# 1_P1.net
KiCad netlist of a schematic drawn in Altium Designer
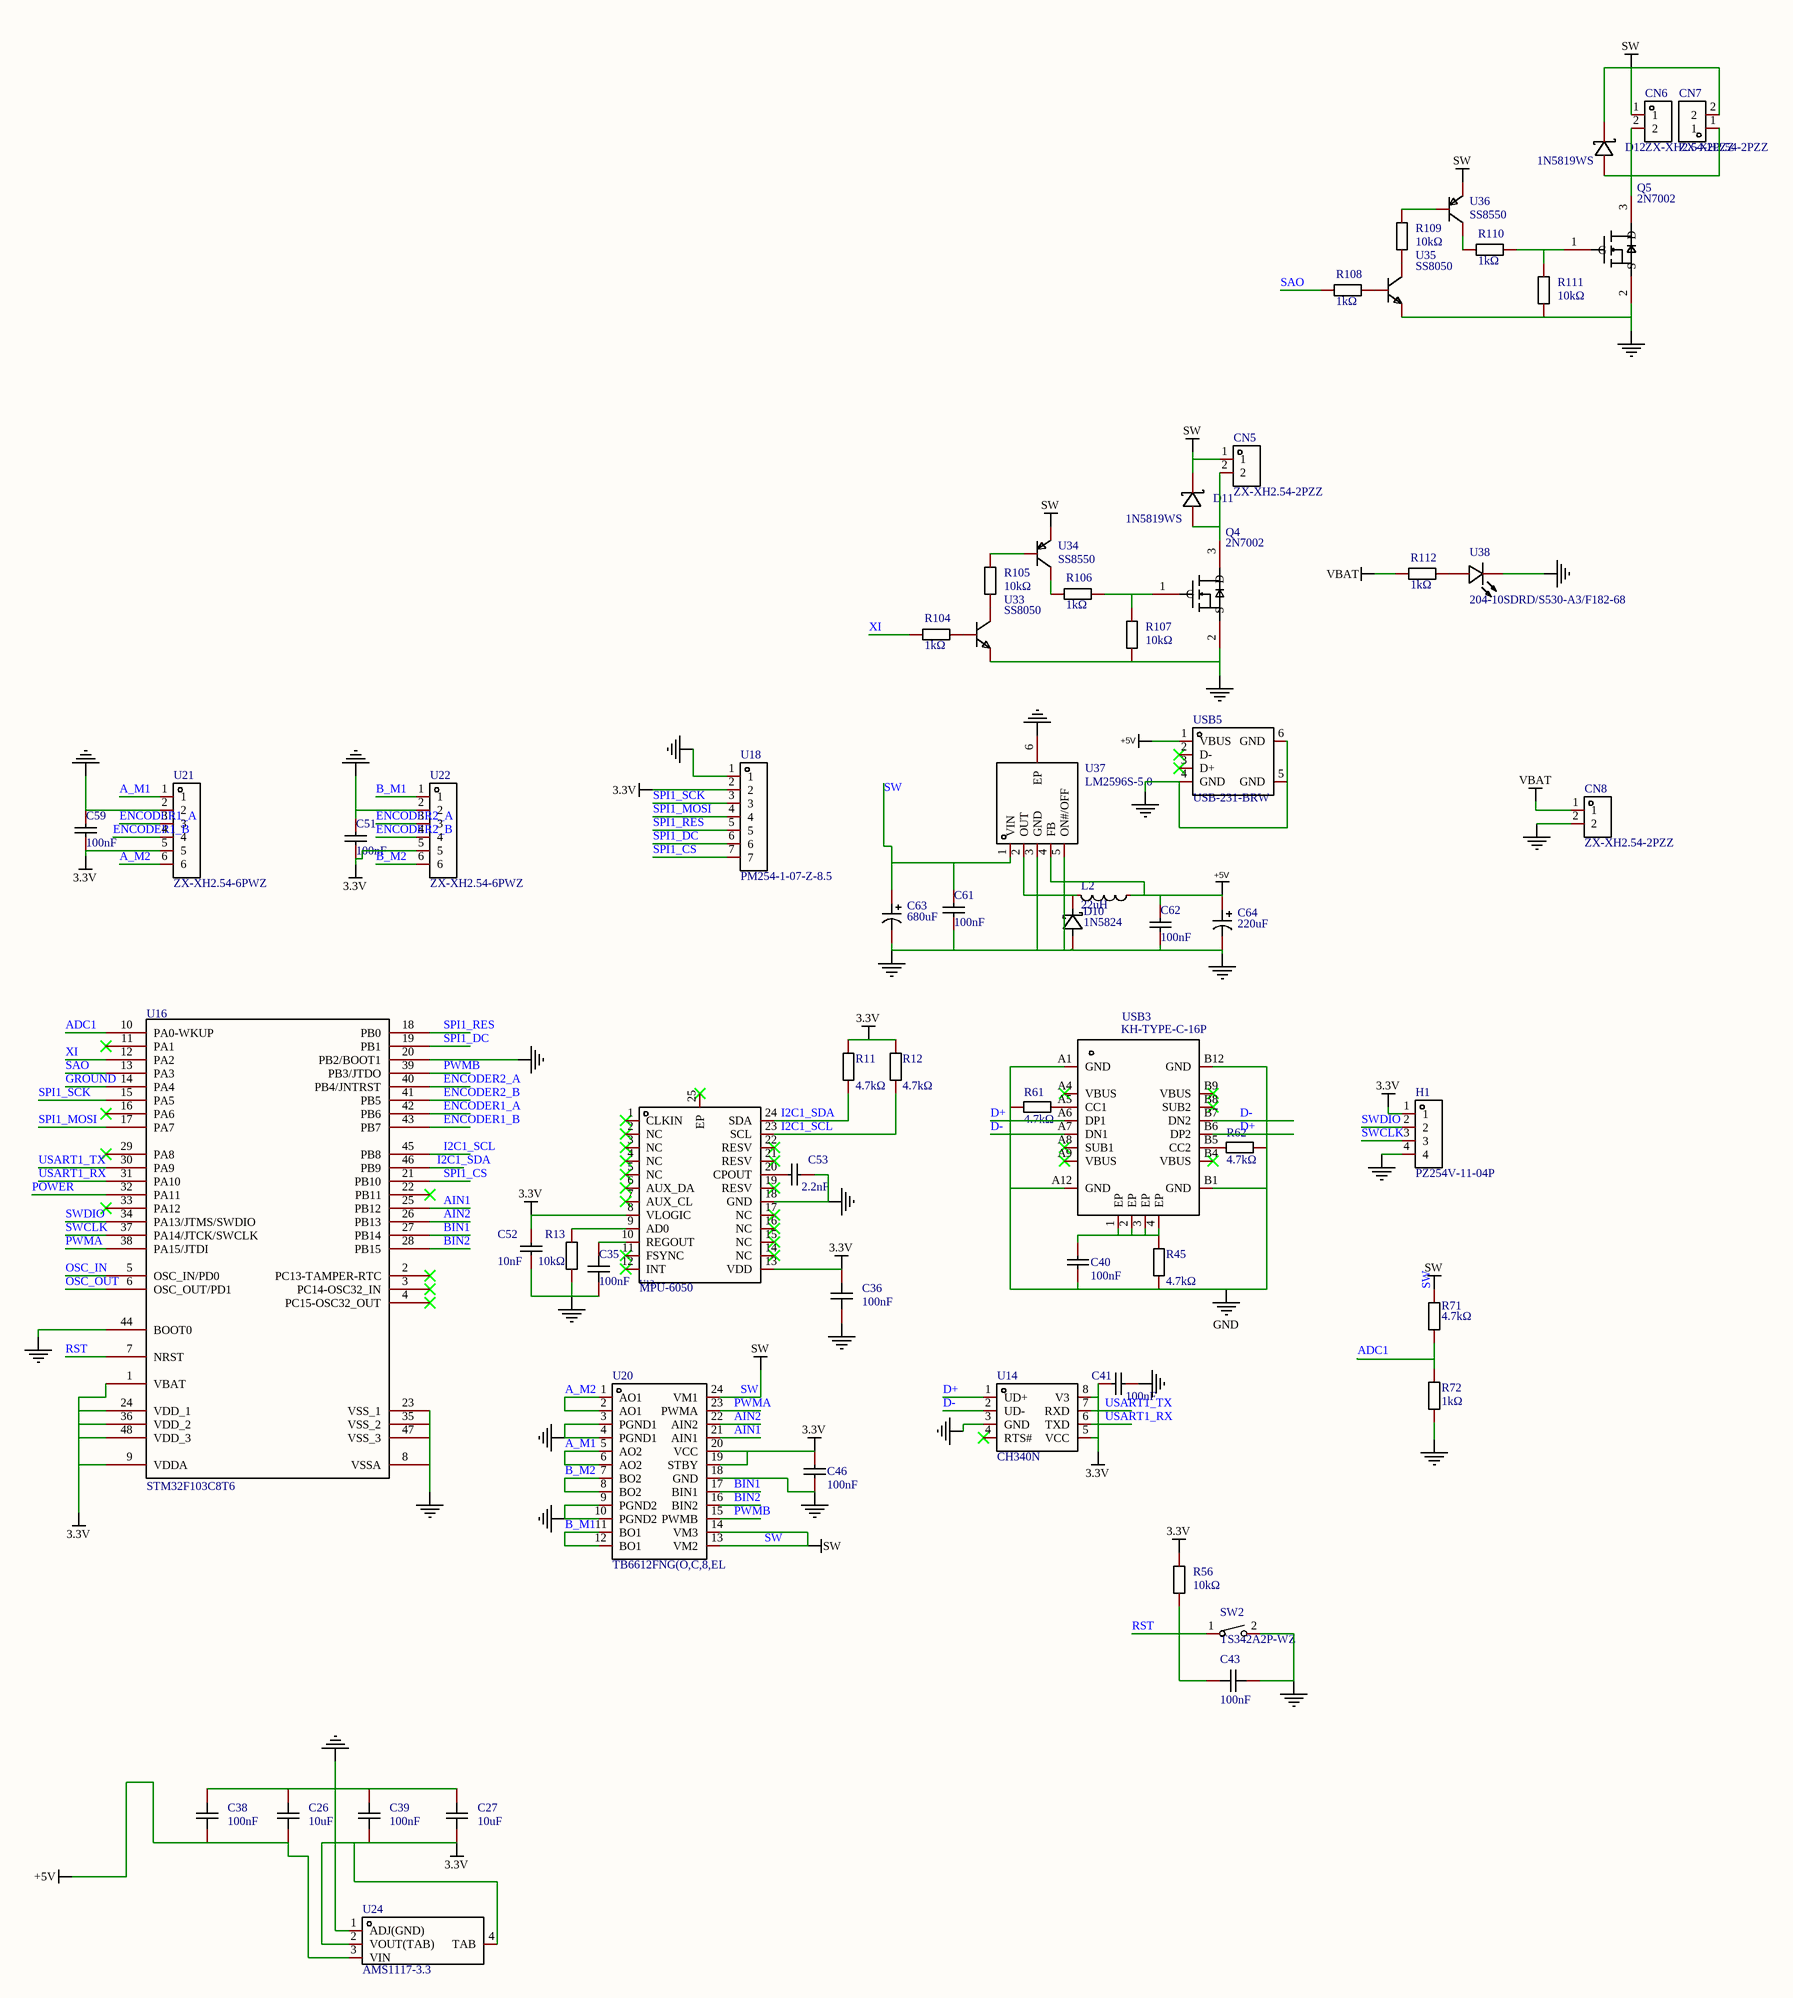
[diagram p0: 1_P1.schdoc]

(export (version "E")
  (design (tool "Eeschema 10.0.6"))
  (components
    (comp (ref "C26")
      (value "10uF")
      (description "容值:10uF;精度:±10%;额定电压:10V;材质(温度系数):X5R;")
      (fields
        (field (name "NAME") "10uF")
        (field (name "MANUFACTURER") "SAMSUNG(三星)")
        (field (name "MANUFACTURER PART") "CL10A106KP8NNNC")
      )
      (libsource (lib "altium-import") (part "root_1_CL10A106KP8NNNC_"))
    )
    (comp (ref "C27")
      (value "10uF")
      (description "容值:10uF;精度:±10%;额定电压:10V;材质(温度系数):X5R;")
      (fields
        (field (name "NAME") "10uF")
        (field (name "MANUFACTURER") "SAMSUNG(三星)")
        (field (name "MANUFACTURER PART") "CL10A106KP8NNNC")
      )
      (libsource (lib "altium-import") (part "root_1_CL10A106KP8NNNC_"))
    )
    (comp (ref "C35")
      (value "100nF")
      (description "容值:100nF;精度:±10%;额定电压:50V;材质(温度系数):X7R;")
      (fields
        (field (name "NAME") "100nF")
        (field (name "MANUFACTURER") "YAGEO(国巨)")
        (field (name "MANUFACTURER PART") "CC0603KRX7R9BB104")
      )
      (libsource (lib "altium-import") (part "root_1_CC0603KRX7R9BB104_"))
    )
    (comp (ref "C36")
      (value "100nF")
      (description "容值:100nF;精度:±10%;额定电压:50V;材质(温度系数):X7R;")
      (fields
        (field (name "NAME") "100nF")
        (field (name "MANUFACTURER") "YAGEO(国巨)")
        (field (name "MANUFACTURER PART") "CC0603KRX7R9BB104")
      )
      (libsource (lib "altium-import") (part "root_1_CC0603KRX7R9BB104_"))
    )
    (comp (ref "C38")
      (value "100nF")
      (description "容值:100nF;精度:±10%;额定电压:50V;材质(温度系数):X7R;")
      (fields
        (field (name "NAME") "100nF")
        (field (name "MANUFACTURER") "YAGEO(国巨)")
        (field (name "MANUFACTURER PART") "CC0603KRX7R9BB104")
      )
      (libsource (lib "altium-import") (part "root_1_CC0603KRX7R9BB104_"))
    )
    (comp (ref "C39")
      (value "100nF")
      (description "容值:100nF;精度:±10%;额定电压:50V;材质(温度系数):X7R;")
      (fields
        (field (name "NAME") "100nF")
        (field (name "MANUFACTURER") "YAGEO(国巨)")
        (field (name "MANUFACTURER PART") "CC0603KRX7R9BB104")
      )
      (libsource (lib "altium-import") (part "root_1_CC0603KRX7R9BB104_"))
    )
    (comp (ref "C40")
      (value "100nF")
      (description "容值:100nF;精度:±10%;额定电压:50V;材质(温度系数):X7R;")
      (fields
        (field (name "NAME") "100nF")
        (field (name "MANUFACTURER") "FH(风华)")
        (field (name "MANUFACTURER PART") "0603B104K500NT")
        (field (name "PUBLISHER") "Altium Limited")
      )
      (libsource (lib "altium-import") (part "root_3_0603B104K500NT_"))
    )
    (comp (ref "C41")
      (value "100nF")
      (description "容值:100nF;精度:±10%;额定电压:50V;材质(温度系数):X7R;")
      (fields
        (field (name "NAME") "100nF")
        (field (name "MANUFACTURER") "FH(风华)")
        (field (name "MANUFACTURER PART") "0603B104K500NT")
        (field (name "PUBLISHER") "Altium Limited")
      )
      (libsource (lib "altium-import") (part "root_0_0603B104K500NT_"))
    )
    (comp (ref "C43")
      (value "100nF")
      (description "容值:100nF;精度:±10%;额定电压:50V;材质(温度系数):X7R;")
      (fields
        (field (name "NAME") "100nF")
        (field (name "MANUFACTURER") "YAGEO(国巨)")
        (field (name "MANUFACTURER PART") "CC0603KRX7R9BB104")
      )
      (libsource (lib "altium-import") (part "root_2_CC0603KRX7R9BB104_"))
    )
    (comp (ref "C46")
      (value "100nF")
      (description "容值:100nF;精度:±10%;额定电压:50V;材质(温度系数):X7R;")
      (fields
        (field (name "NAME") "100nF")
        (field (name "MANUFACTURER") "FH(风华)")
        (field (name "MANUFACTURER PART") "0603B104K500NT")
        (field (name "PUBLISHER") "Altium Limited")
      )
      (libsource (lib "altium-import") (part "root_3_0603B104K500NT_"))
    )
    (comp (ref "C51")
      (value "100nF")
      (description "容值:100nF;精度:±10%;额定电压:50V;材质(温度系数):X7R;")
      (fields
        (field (name "NAME") "100nF")
        (field (name "MANUFACTURER") "FH(风华)")
        (field (name "MANUFACTURER PART") "0603B104K500NT")
        (field (name "PUBLISHER") "Altium Limited")
      )
      (libsource (lib "altium-import") (part "root_3_0603B104K500NT_"))
    )
    (comp (ref "C52")
      (value "10nF")
      (description "容值:10nF;精度:±10%;额定电压:50V;材质(温度系数):X7R;")
      (fields
        (field (name "NAME") "10nF")
        (field (name "MANUFACTURER") "YAGEO(国巨)")
        (field (name "MANUFACTURER PART") "CC0603KRX7R9BB103")
      )
      (libsource (lib "altium-import") (part "root_3_CC0603KRX7R9BB103_"))
    )
    (comp (ref "C53")
      (value "2.2nF")
      (description "容值:2.2nF;精度:±10%;额定电压:50V;材质(温度系数):X7R;")
      (fields
        (field (name "NAME") "2.2nF")
        (field (name "MANUFACTURER") "FH(风华)")
        (field (name "MANUFACTURER PART") "0603B222K500NT")
      )
      (libsource (lib "altium-import") (part "root_0_0603B222K500NT_"))
    )
    (comp (ref "C59")
      (value "100nF")
      (description "容值:100nF;精度:±10%;额定电压:50V;材质(温度系数):X7R;")
      (fields
        (field (name "NAME") "100nF")
        (field (name "MANUFACTURER") "FH(风华)")
        (field (name "MANUFACTURER PART") "0603B104K500NT")
        (field (name "PUBLISHER") "Altium Limited")
      )
      (libsource (lib "altium-import") (part "root_2_0603B104K500NT_"))
    )
    (comp (ref "C61")
      (value "100nF")
      (description "容值:100nF;精度:±10%;额定电压:50V;材质(温度系数):X7R;")
      (fields
        (field (name "NAME") "100nF")
        (field (name "MANUFACTURER") "FH(风华)")
        (field (name "MANUFACTURER PART") "0603B104K500NT")
        (field (name "PUBLISHER") "Altium Limited")
      )
      (libsource (lib "altium-import") (part "root_3_0603B104K500NT_"))
    )
    (comp (ref "C62")
      (value "100nF")
      (description "容值:100nF;精度:±10%;额定电压:50V;材质(温度系数):X7R;")
      (fields
        (field (name "NAME") "100nF")
        (field (name "MANUFACTURER") "FH(风华)")
        (field (name "MANUFACTURER PART") "0603B104K500NT")
        (field (name "PUBLISHER") "Altium Limited")
      )
      (libsource (lib "altium-import") (part "root_3_0603B104K500NT_"))
    )
    (comp (ref "C63")
      (value "680uF")
      (description "容值:680uF;精度:±20%;额定电压:35V;纹波电流:-;等效串联电阻:-;")
      (fields
        (field (name "NAME") "680uF")
        (field (name "MANUFACTURER") "AISHI(艾华集团)")
        (field (name "MANUFACTURER PART") "ERS1VM681G16OT")
      )
      (libsource (lib "altium-import") (part "root_3_ERS1VM681G16OT_"))
    )
    (comp (ref "C64")
      (value "220uF")
      (description "容值:220uF;精度:±20%;额定电压:50V;纹波电流:350mA@120kHz;等效串联电阻:-;")
      (fields
        (field (name "NAME") "220uF")
        (field (name "MANUFACTURER") "KNSCHA(科尼盛)")
        (field (name "MANUFACTURER PART") "01EC3470")
      )
      (libsource (lib "altium-import") (part "root_3_01EC3470_"))
    )
    (comp (ref "CN5")
      (value "ZX-XH2.54-2PZZ")
      (fields (field (name "NAME") "ZX-XH2.54-2PZZ") (field (name "MANUFACTURER") "Megastar(兆星)"))
      (libsource (lib "altium-import") (part "root_0_ZX-XH2.54-2PZZ_"))
    )
    (comp (ref "CN6")
      (value "ZX-XH2.54-2PZZ")
      (fields (field (name "NAME") "ZX-XH2.54-2PZZ") (field (name "MANUFACTURER") "Megastar(兆星)"))
      (libsource (lib "altium-import") (part "root_0_ZX-XH2.54-2PZZ_"))
    )
    (comp (ref "CN7")
      (value "ZX-XH2.54-2PZZ")
      (fields (field (name "NAME") "ZX-XH2.54-2PZZ") (field (name "MANUFACTURER") "Megastar(兆星)"))
      (libsource (lib "altium-import") (part "root_2_ZX-XH2.54-2PZZ_"))
    )
    (comp (ref "CN8")
      (value "ZX-XH2.54-2PZZ")
      (fields (field (name "NAME") "ZX-XH2.54-2PZZ") (field (name "MANUFACTURER") "Megastar(兆星)"))
      (libsource (lib "altium-import") (part "root_0_ZX-XH2.54-2PZZ_"))
    )
    (comp (ref "D10")
      (value "1N5824")
      (description "二极管配置:独立式;正向压降(Vf):550mV@5A;直流反向耐压(Vr):30V;平均整流电流(Io):5A;")
      (fields (field (name "NAME") "1N5824") (field (name "MANUFACTURER") "FUXINSEMI(富芯森美)"))
      (libsource (lib "altium-import") (part "root_3_1N5824_C7503125_"))
    )
    (comp (ref "D11")
      (value "1N5819WS")
      (description "正向压降(Vf):600mV@1A;直流反向耐压(Vr):40V;整流电流:1A;")
      (fields (field (name "NAME") "1N5819WS") (field (name "MANUFACTURER") "Hottech(合科泰)"))
      (libsource (lib "altium-import") (part "root_3_1N5819WS_C191023_"))
    )
    (comp (ref "D12")
      (value "1N5819WS")
      (description "正向压降(Vf):600mV@1A;直流反向耐压(Vr):40V;整流电流:1A;")
      (fields (field (name "NAME") "1N5819WS") (field (name "MANUFACTURER") "Hottech(合科泰)"))
      (libsource (lib "altium-import") (part "root_3_1N5819WS_C191023_"))
    )
    (comp (ref "H1")
      (value "PZ254V-11-04P")
      (fields (field (name "NAME") "PZ254V-11-04P") (field (name "MANUFACTURER") "XFCN(兴飞)"))
      (libsource (lib "altium-import") (part "root_0_PZ254V-11-04P_"))
    )
    (comp (ref "L2")
      (value "22uH")
      (description "电感值:22uH;精度:±20%;额定电流:-;")
      (fields
        (field (name "NAME") "22uH")
        (field (name "MANUFACTURER") "Sunltech(韩国顺磁)")
        (field (name "MANUFACTURER PART") "SLO0630H220MTT")
      )
      (libsource (lib "altium-import") (part "root_2_SLO0630H220MTT_"))
    )
    (comp (ref "Q4")
      (value "2N7002")
      (fields (field (name "NAME") "2N7002") (field (name "MANUFACTURER") "JSMSEMI(杰盛微)"))
      (libsource (lib "altium-import") (part "root_0_2N7002_C916396_"))
    )
    (comp (ref "Q5")
      (value "2N7002")
      (fields (field (name "NAME") "2N7002") (field (name "MANUFACTURER") "JSMSEMI(杰盛微)"))
      (libsource (lib "altium-import") (part "root_0_2N7002_C916396_"))
    )
    (comp (ref "R11")
      (value "4.7kΩ")
      (description "电阻类型:厚膜电阻;阻值:4.7kΩ;精度:±1%;功率:100mW;最大工作电压:75V;温度系数:±100ppm/℃;")
      (fields
        (field (name "NAME") "4.7kΩ")
        (field (name "MANUFACTURER") "UNI-ROYAL(厚声)")
        (field (name "MANUFACTURER PART") "0603WAF4701T5E")
      )
      (libsource (lib "altium-import") (part "root_1_0603WAF4701T5E_"))
    )
    (comp (ref "R12")
      (value "4.7kΩ")
      (description "电阻类型:厚膜电阻;阻值:4.7kΩ;精度:±1%;功率:100mW;最大工作电压:75V;温度系数:±100ppm/℃;")
      (fields
        (field (name "NAME") "4.7kΩ")
        (field (name "MANUFACTURER") "UNI-ROYAL(厚声)")
        (field (name "MANUFACTURER PART") "0603WAF4701T5E")
      )
      (libsource (lib "altium-import") (part "root_1_0603WAF4701T5E_"))
    )
    (comp (ref "R13")
      (value "10kΩ")
      (description "电阻类型:薄膜电阻;阻值:10kΩ;精度:±0.1%;功率:125mW;")
      (fields
        (field (name "NAME") "10kΩ")
        (field (name "MANUFACTURER") "YAGEO(国巨)")
        (field (name "MANUFACTURER PART") "RT0805BRD0710KL")
      )
      (libsource (lib "altium-import") (part "root_1_RT0805BRD0710KL_"))
    )
    (comp (ref "R45")
      (value "4.7kΩ")
      (description "电阻类型:厚膜电阻;阻值:4.7kΩ;精度:±1%;功率:100mW;最大工作电压:75V;温度系数:±100ppm/℃;")
      (fields
        (field (name "NAME") "4.7kΩ")
        (field (name "MANUFACTURER") "UNI-ROYAL(厚声)")
        (field (name "MANUFACTURER PART") "0603WAF4701T5E")
      )
      (libsource (lib "altium-import") (part "root_1_0603WAF4701T5E_"))
    )
    (comp (ref "R56")
      (value "10kΩ")
      (description "电阻类型:薄膜电阻;阻值:10kΩ;精度:±0.1%;功率:125mW;")
      (fields
        (field (name "NAME") "10kΩ")
        (field (name "MANUFACTURER") "YAGEO(国巨)")
        (field (name "MANUFACTURER PART") "RT0805BRD0710KL")
      )
      (libsource (lib "altium-import") (part "root_1_RT0805BRD0710KL_"))
    )
    (comp (ref "R61")
      (value "4.7kΩ")
      (description "电阻类型:厚膜电阻;阻值:4.7kΩ;精度:±1%;功率:100mW;最大工作电压:75V;温度系数:±100ppm/℃;")
      (fields
        (field (name "NAME") "4.7kΩ")
        (field (name "MANUFACTURER") "UNI-ROYAL(厚声)")
        (field (name "MANUFACTURER PART") "0603WAF4701T5E")
      )
      (libsource (lib "altium-import") (part "root_0_0603WAF4701T5E_"))
    )
    (comp (ref "R62")
      (value "4.7kΩ")
      (description "电阻类型:厚膜电阻;阻值:4.7kΩ;精度:±1%;功率:100mW;最大工作电压:75V;温度系数:±100ppm/℃;")
      (fields
        (field (name "NAME") "4.7kΩ")
        (field (name "MANUFACTURER") "UNI-ROYAL(厚声)")
        (field (name "MANUFACTURER PART") "0603WAF4701T5E")
      )
      (libsource (lib "altium-import") (part "root_0_0603WAF4701T5E_"))
    )
    (comp (ref "R71")
      (value "4.7kΩ")
      (description "电阻类型:厚膜电阻;阻值:4.7kΩ;精度:±1%;功率:100mW;最大工作电压:75V;温度系数:±100ppm/℃;")
      (fields
        (field (name "NAME") "4.7kΩ")
        (field (name "MANUFACTURER") "UNI-ROYAL(厚声)")
        (field (name "MANUFACTURER PART") "0603WAF4701T5E")
      )
      (libsource (lib "altium-import") (part "root_1_0603WAF4701T5E_"))
    )
    (comp (ref "R72")
      (value "1kΩ")
      (description "电阻类型:厚膜电阻;阻值:1kΩ;精度:±1%;功率:100mW;最大工作电压:75V;温度系数:±100ppm/℃;")
      (fields
        (field (name "NAME") "1kΩ")
        (field (name "MANUFACTURER") "UNI-ROYAL(厚声)")
        (field (name "MANUFACTURER PART") "0603WAF1001T5E")
      )
      (libsource (lib "altium-import") (part "root_1_0603WAF1001T5E_"))
    )
    (comp (ref "R104")
      (value "1kΩ")
      (description "电阻类型:厚膜电阻;阻值:1kΩ;精度:±1%;功率:100mW;最大工作电压:75V;温度系数:±100ppm/℃;")
      (fields
        (field (name "NAME") "1kΩ")
        (field (name "MANUFACTURER") "UNI-ROYAL(厚声)")
        (field (name "MANUFACTURER PART") "0603WAF1001T5E")
      )
      (libsource (lib "altium-import") (part "root_2_0603WAF1001T5E_"))
    )
    (comp (ref "R105")
      (value "10kΩ")
      (description "电阻类型:薄膜电阻;阻值:10kΩ;精度:±0.1%;功率:125mW;")
      (fields
        (field (name "NAME") "10kΩ")
        (field (name "MANUFACTURER") "YAGEO(国巨)")
        (field (name "MANUFACTURER PART") "RT0805BRD0710KL")
      )
      (libsource (lib "altium-import") (part "root_1_RT0805BRD0710KL_"))
    )
    (comp (ref "R106")
      (value "1kΩ")
      (description "电阻类型:厚膜电阻;阻值:1kΩ;精度:±1%;功率:100mW;最大工作电压:75V;温度系数:±100ppm/℃;")
      (fields
        (field (name "NAME") "1kΩ")
        (field (name "MANUFACTURER") "UNI-ROYAL(厚声)")
        (field (name "MANUFACTURER PART") "0603WAF1001T5E")
      )
      (libsource (lib "altium-import") (part "root_2_0603WAF1001T5E_"))
    )
    (comp (ref "R107")
      (value "10kΩ")
      (description "电阻类型:薄膜电阻;阻值:10kΩ;精度:±0.1%;功率:125mW;")
      (fields
        (field (name "NAME") "10kΩ")
        (field (name "MANUFACTURER") "YAGEO(国巨)")
        (field (name "MANUFACTURER PART") "RT0805BRD0710KL")
      )
      (libsource (lib "altium-import") (part "root_1_RT0805BRD0710KL_"))
    )
    (comp (ref "R108")
      (value "1kΩ")
      (description "电阻类型:厚膜电阻;阻值:1kΩ;精度:±1%;功率:100mW;最大工作电压:75V;温度系数:±100ppm/℃;")
      (fields
        (field (name "NAME") "1kΩ")
        (field (name "MANUFACTURER") "UNI-ROYAL(厚声)")
        (field (name "MANUFACTURER PART") "0603WAF1001T5E")
      )
      (libsource (lib "altium-import") (part "root_2_0603WAF1001T5E_"))
    )
    (comp (ref "R109")
      (value "10kΩ")
      (description "电阻类型:薄膜电阻;阻值:10kΩ;精度:±0.1%;功率:125mW;")
      (fields
        (field (name "NAME") "10kΩ")
        (field (name "MANUFACTURER") "YAGEO(国巨)")
        (field (name "MANUFACTURER PART") "RT0805BRD0710KL")
      )
      (libsource (lib "altium-import") (part "root_1_RT0805BRD0710KL_"))
    )
    (comp (ref "R110")
      (value "1kΩ")
      (description "电阻类型:厚膜电阻;阻值:1kΩ;精度:±1%;功率:100mW;最大工作电压:75V;温度系数:±100ppm/℃;")
      (fields
        (field (name "NAME") "1kΩ")
        (field (name "MANUFACTURER") "UNI-ROYAL(厚声)")
        (field (name "MANUFACTURER PART") "0603WAF1001T5E")
      )
      (libsource (lib "altium-import") (part "root_2_0603WAF1001T5E_"))
    )
    (comp (ref "R111")
      (value "10kΩ")
      (description "电阻类型:薄膜电阻;阻值:10kΩ;精度:±0.1%;功率:125mW;")
      (fields
        (field (name "NAME") "10kΩ")
        (field (name "MANUFACTURER") "YAGEO(国巨)")
        (field (name "MANUFACTURER PART") "RT0805BRD0710KL")
      )
      (libsource (lib "altium-import") (part "root_1_RT0805BRD0710KL_"))
    )
    (comp (ref "R112")
      (value "1kΩ")
      (description "电阻类型:厚膜电阻;阻值:1kΩ;精度:±1%;功率:100mW;最大工作电压:75V;温度系数:±100ppm/℃;")
      (fields
        (field (name "NAME") "1kΩ")
        (field (name "MANUFACTURER") "UNI-ROYAL(厚声)")
        (field (name "MANUFACTURER PART") "0603WAF1001T5E")
      )
      (libsource (lib "altium-import") (part "root_2_0603WAF1001T5E_"))
    )
    (comp (ref "SW2")
      (value "TS342A2P-WZ")
      (description "电路结构:单刀单掷;带支架:否;触点电流:50mA;额定电压(DC):12V;安装方式:立贴;绝缘电阻:100MΩ;机械寿命:3万次;")
      (fields (field (name "NAME") "TS342A2P-WZ") (field (name "MANUFACTURER") "SHOU HAN(首韩)"))
      (libsource (lib "altium-import") (part "root_0_TS342A2P-WZ_"))
    )
    (comp (ref "U12")
      (value "MPU-6050")
      (description "三轴加速度计和三轴陀螺仪，工作电压：2.375V~3.46V")
      (fields (field (name "NAME") "MPU-6050") (field (name "MANUFACTURER") "TDK InvenSense(应美盛)"))
      (libsource (lib "altium-import") (part "root_0_MPU-6050_"))
    )
    (comp (ref "U14")
      (value "CH340N")
      (fields (field (name "NAME") "CH340N") (field (name "MANUFACTURER") "WCH(南京沁恒)"))
      (libsource (lib "altium-import") (part "root_0_CH340N_"))
    )
    (comp (ref "U16")
      (value "STM32F103C8T6")
      (description "CPU内核:CM3;程序存储容量:64KB;RAM总容量:20KB;GPIO端口数量:37;工作电压范围:2V~3.6V;CPU最大主频:72MHz;程序存储器类型:FLASH;")
      (fields
        (field (name "NAME") "STM32F103C8T6")
        (field (name "MANUFACTURER") "ST(意法半导体)")
        (field (name "PUBLISHER") "Altium Limited")
      )
      (libsource (lib "altium-import") (part "root_0_STM32F103C8T6_"))
    )
    (comp (ref "U18")
      (value "PM254-1-07-Z-8.5")
      (fields (field (name "NAME") "PM254-1-07-Z-8.5") (field (name "MANUFACTURER") "HCTL(华灿天禄)"))
      (libsource (lib "altium-import") (part "root_0_PM254-1-07-Z-8.5_"))
    )
    (comp (ref "U20")
      (value "TB6612FNG(O,C,8,EL")
      (description "双直流电机驱动器集成电路")
      (fields (field (name "NAME") "TB6612FNG(O,C,8,EL") (field (name "MANUFACTURER") "TOSHIBA(东芝)"))
      (libsource (lib "altium-import") (part "root_0_TB6612FNG(O,C,8,EL_"))
    )
    (comp (ref "U21")
      (value "ZX-XH2.54-6PWZ")
      (fields (field (name "NAME") "ZX-XH2.54-6PWZ") (field (name "MANUFACTURER") "Megastar(兆星)"))
      (libsource (lib "altium-import") (part "root_0_ZX-XH2.54-6PWZ_"))
    )
    (comp (ref "U22")
      (value "ZX-XH2.54-6PWZ")
      (fields (field (name "NAME") "ZX-XH2.54-6PWZ") (field (name "MANUFACTURER") "Megastar(兆星)"))
      (libsource (lib "altium-import") (part "root_0_ZX-XH2.54-6PWZ_"))
    )
    (comp (ref "U24")
      (value "AMS1117-3.3")
      (description "输出类型:固定;最大输入电压:12V;输出电压:5V;最大输出电流:1A;电源纹波抑制比(PSRR):60dB@(120Hz);输出极性:正极;")
      (fields (field (name "NAME") "AMS1117-3.3") (field (name "MANUFACTURER") "UMW(友台半导体)"))
      (libsource (lib "altium-import") (part "root_0_AMS1117-5.0_C347223_"))
    )
    (comp (ref "U33")
      (value "SS8050")
      (description "晶体管类型:NPN;集电极电流(Ic):1.5A;集射极击穿电压(Vceo):25V;功率(Pd):300mW;直流电流增益(hFE@Ic,Vce):120@100mA,1.0V;")
      (fields (field (name "NAME") "SS8050") (field (name "MANUFACTURER") "宏迦橙"))
      (libsource (lib "altium-import") (part "root_0_SS8050_C7420370_"))
    )
    (comp (ref "U34")
      (value "SS8550")
      (description "晶体管类型:PNP;集电极电流(Ic):1.5A;集射极击穿电压(Vceo):25V;功率(Pd):300mW;直流电流增益(hFE@Ic,Vce):120@100mA,1.0V;")
      (fields (field (name "NAME") "SS8550") (field (name "MANUFACTURER") "宏迦橙"))
      (libsource (lib "altium-import") (part "root_2_mirrored_SS8550_C7420371_"))
    )
    (comp (ref "U35")
      (value "SS8050")
      (description "晶体管类型:NPN;集电极电流(Ic):1.5A;集射极击穿电压(Vceo):25V;功率(Pd):300mW;直流电流增益(hFE@Ic,Vce):120@100mA,1.0V;")
      (fields (field (name "NAME") "SS8050") (field (name "MANUFACTURER") "宏迦橙"))
      (libsource (lib "altium-import") (part "root_0_SS8050_C7420370_"))
    )
    (comp (ref "U36")
      (value "SS8550")
      (description "晶体管类型:PNP;集电极电流(Ic):1.5A;集射极击穿电压(Vceo):25V;功率(Pd):300mW;直流电流增益(hFE@Ic,Vce):120@100mA,1.0V;")
      (fields (field (name "NAME") "SS8550") (field (name "MANUFACTURER") "宏迦橙"))
      (libsource (lib "altium-import") (part "root_2_mirrored_SS8550_C7420371_"))
    )
    (comp (ref "U37")
      (value "LM2596S-5.0")
      (description "功能类型:降压型;输出类型:固定;输入电压:40V;输出电压:5V;输出电流:3A;")
      (fields (field (name "NAME") "LM2596S-5.0") (field (name "MANUFACTURER") "UMW(友台半导体)"))
      (libsource (lib "altium-import") (part "root_3_LM2596S-5.0_C347421_"))
    )
    (comp (ref "U38")
      (value "204-10SDRD/S530-A3/F182-68")
      (fields
        (field (name "NAME") "204-10SDRD/S530-A3/F182-68")
        (field (name "MANUFACTURER") "EVERLIGHT(亿光)")
      )
      (libsource (lib "altium-import") (part "root_2_204-10SDRD/S530-A3/F182-68_"))
    )
    (comp (ref "USB3")
      (value "KH-TYPE-C-16P")
      (description "连接器类型:Type-C;标准:-;公母:母;端口数量:1;触点数量:16P;安装方式:卧贴;额定电流 - 电源:3A;工作温度范围:-40℃~+85℃;")
      (fields (field (name "NAME") "KH-TYPE-C-16P") (field (name "MANUFACTURER") "kinghelm(金航标)"))
      (libsource (lib "altium-import") (part "root_0_KH-TYPE-C-16P_"))
    )
    (comp (ref "USB5")
      (value "USB-231-BRW")
      (fields (field (name "NAME") "USB-231-BRW") (field (name "MANUFACTURER") "XUNPU(讯普)"))
      (libsource (lib "altium-import") (part "root_0_USB-231-BRW_"))
    )
  )
  (nets
    (net (code "1") (name "+5V") (class "Default")
      (node (ref "C26") (pin "1") (pinfunction "1_1") (pintype "passive"))
      (node (ref "C38") (pin "1") (pinfunction "1_1") (pintype "passive"))
      (node (ref "C62") (pin "1") (pinfunction "1_1") (pintype "passive"))
      (node (ref "C64") (pin "1") (pinfunction "1_1") (pintype "passive"))
      (node (ref "L2") (pin "1") (pinfunction "1_1") (pintype "passive"))
      (node (ref "U24") (pin "3") (pinfunction "VIN_3") (pintype "passive"))
      (node (ref "U37") (pin "4") (pinfunction "FB_4") (pintype "passive"))
      (node (ref "USB5") (pin "1") (pinfunction "VBUS_1") (pintype "passive"))
    )
    (net (code "2") (name "/ADC1") (class "Default")
      (node (ref "R71") (pin "1") (pinfunction "1_1") (pintype "passive"))
      (node (ref "R72") (pin "2") (pinfunction "2_2") (pintype "passive"))
      (node (ref "U16") (pin "10") (pinfunction "PA0-WKUP_10") (pintype "passive"))
    )
    (net (code "3") (name "/AIN1") (class "Default")
      (node (ref "U16") (pin "25") (pinfunction "PB12_25") (pintype "passive"))
      (node (ref "U20") (pin "21") (pinfunction "AIN1_21") (pintype "passive"))
    )
    (net (code "4") (name "/AIN2") (class "Default")
      (node (ref "U16") (pin "26") (pinfunction "PB13_26") (pintype "passive"))
      (node (ref "U20") (pin "22") (pinfunction "AIN2_22") (pintype "passive"))
    )
    (net (code "5") (name "/A_M1") (class "Default")
      (node (ref "U20") (pin "5") (pinfunction "AO2_5") (pintype "passive"))
      (node (ref "U20") (pin "6") (pinfunction "AO2_6") (pintype "passive"))
      (node (ref "U21") (pin "1") (pinfunction "1_1") (pintype "passive"))
    )
    (net (code "6") (name "/A_M2") (class "Default")
      (node (ref "U20") (pin "1") (pinfunction "AO1_1") (pintype "passive"))
      (node (ref "U20") (pin "2") (pinfunction "AO1_2") (pintype "passive"))
      (node (ref "U21") (pin "6") (pinfunction "6_6") (pintype "passive"))
    )
    (net (code "7") (name "/BIN1") (class "Default")
      (node (ref "U16") (pin "27") (pinfunction "PB14_27") (pintype "passive"))
      (node (ref "U20") (pin "17") (pinfunction "BIN1_17") (pintype "passive"))
    )
    (net (code "8") (name "/BIN2") (class "Default")
      (node (ref "U16") (pin "28") (pinfunction "PB15_28") (pintype "passive"))
      (node (ref "U20") (pin "16") (pinfunction "BIN2_16") (pintype "passive"))
    )
    (net (code "9") (name "/B_M1") (class "Default")
      (node (ref "U20") (pin "11") (pinfunction "BO1_11") (pintype "passive"))
      (node (ref "U20") (pin "12") (pinfunction "BO1_12") (pintype "passive"))
      (node (ref "U22") (pin "1") (pinfunction "1_1") (pintype "passive"))
    )
    (net (code "10") (name "/B_M2") (class "Default")
      (node (ref "U20") (pin "7") (pinfunction "BO2_7") (pintype "passive"))
      (node (ref "U20") (pin "8") (pinfunction "BO2_8") (pintype "passive"))
      (node (ref "U22") (pin "6") (pinfunction "6_6") (pintype "passive"))
    )
    (net (code "11") (name "/D+") (class "Default")
      (node (ref "U14") (pin "1") (pinfunction "UD+_1") (pintype "passive"))
      (node (ref "USB3") (pin "A6") (pinfunction "DP1_A6") (pintype "passive"))
      (node (ref "USB3") (pin "B6") (pinfunction "DP2_B6") (pintype "passive"))
    )
    (net (code "12") (name "/D-") (class "Default")
      (node (ref "U14") (pin "2") (pinfunction "UD-_2") (pintype "passive"))
      (node (ref "USB3") (pin "A7") (pinfunction "DN1_A7") (pintype "passive"))
      (node (ref "USB3") (pin "B7") (pinfunction "DN2_B7") (pintype "passive"))
    )
    (net (code "13") (name "/ENCODER1_A") (class "Default")
      (node (ref "U16") (pin "42") (pinfunction "PB6_42") (pintype "passive"))
      (node (ref "U21") (pin "3") (pinfunction "3_3") (pintype "passive"))
    )
    (net (code "14") (name "/ENCODER1_B") (class "Default")
      (node (ref "U16") (pin "43") (pinfunction "PB7_43") (pintype "passive"))
      (node (ref "U21") (pin "4") (pinfunction "4_4") (pintype "passive"))
    )
    (net (code "15") (name "/ENCODER2_A") (class "Default")
      (node (ref "U16") (pin "40") (pinfunction "PB4/JNTRST_40") (pintype "passive"))
      (node (ref "U22") (pin "3") (pinfunction "3_3") (pintype "passive"))
    )
    (net (code "16") (name "/ENCODER2_B") (class "Default")
      (node (ref "U16") (pin "41") (pinfunction "PB5_41") (pintype "passive"))
      (node (ref "U22") (pin "4") (pinfunction "4_4") (pintype "passive"))
    )
    (net (code "17") (name "/GROUND") (class "Default")
      (node (ref "U16") (pin "14") (pinfunction "PA4_14") (pintype "passive"))
    )
    (net (code "18") (name "/I2C1_SCL") (class "Default")
      (node (ref "R12") (pin "1") (pinfunction "1_1") (pintype "passive"))
      (node (ref "U12") (pin "23") (pinfunction "SCL_23") (pintype "passive"))
      (node (ref "U16") (pin "45") (pinfunction "PB8_45") (pintype "passive"))
    )
    (net (code "19") (name "/I2C1_SDA") (class "Default")
      (node (ref "R11") (pin "1") (pinfunction "1_1") (pintype "passive"))
      (node (ref "U12") (pin "24") (pinfunction "SDA_24") (pintype "passive"))
      (node (ref "U16") (pin "46") (pinfunction "PB9_46") (pintype "passive"))
    )
    (net (code "20") (name "/OSC_IN") (class "Default")
      (node (ref "U16") (pin "5") (pinfunction "OSC_IN/PD0_5") (pintype "passive"))
    )
    (net (code "21") (name "/OSC_OUT") (class "Default")
      (node (ref "U16") (pin "6") (pinfunction "OSC_OUT/PD1_6") (pintype "passive"))
    )
    (net (code "22") (name "/POWER") (class "Default")
      (node (ref "U16") (pin "32") (pinfunction "PA11_32") (pintype "passive"))
    )
    (net (code "23") (name "/PWMA") (class "Default")
      (node (ref "U16") (pin "38") (pinfunction "PA15/JTDI_38") (pintype "passive"))
      (node (ref "U20") (pin "23") (pinfunction "PWMA_23") (pintype "passive"))
    )
    (net (code "24") (name "/PWMB") (class "Default")
      (node (ref "U16") (pin "39") (pinfunction "PB3/JTDO_39") (pintype "passive"))
      (node (ref "U20") (pin "15") (pinfunction "PWMB_15") (pintype "passive"))
    )
    (net (code "25") (name "/RST") (class "Default")
      (node (ref "C43") (pin "2") (pinfunction "2_2") (pintype "passive"))
      (node (ref "R56") (pin "1") (pinfunction "1_1") (pintype "passive"))
      (node (ref "SW2") (pin "1") (pinfunction "1_1") (pintype "passive"))
      (node (ref "U16") (pin "7") (pinfunction "NRST_7") (pintype "passive"))
    )
    (net (code "26") (name "/SAO") (class "Default")
      (node (ref "R108") (pin "2") (pinfunction "2_2") (pintype "passive"))
      (node (ref "U16") (pin "13") (pinfunction "PA3_13") (pintype "passive"))
    )
    (net (code "27") (name "/SPI1_CS") (class "Default")
      (node (ref "U16") (pin "21") (pinfunction "PB10_21") (pintype "passive"))
      (node (ref "U18") (pin "7") (pinfunction "7_7") (pintype "passive"))
    )
    (net (code "28") (name "/SPI1_DC") (class "Default")
      (node (ref "U16") (pin "19") (pinfunction "PB1_19") (pintype "passive"))
      (node (ref "U18") (pin "6") (pinfunction "6_6") (pintype "passive"))
    )
    (net (code "29") (name "/SPI1_MOSI") (class "Default")
      (node (ref "U16") (pin "17") (pinfunction "PA7_17") (pintype "passive"))
      (node (ref "U18") (pin "4") (pinfunction "4_4") (pintype "passive"))
    )
    (net (code "30") (name "/SPI1_RES") (class "Default")
      (node (ref "U16") (pin "18") (pinfunction "PB0_18") (pintype "passive"))
      (node (ref "U18") (pin "5") (pinfunction "5_5") (pintype "passive"))
    )
    (net (code "31") (name "/SPI1_SCK") (class "Default")
      (node (ref "U16") (pin "15") (pinfunction "PA5_15") (pintype "passive"))
      (node (ref "U18") (pin "3") (pinfunction "3_3") (pintype "passive"))
    )
    (net (code "32") (name "/SWCLK") (class "Default")
      (node (ref "H1") (pin "3") (pinfunction "3_3") (pintype "passive"))
      (node (ref "U16") (pin "37") (pinfunction "PA14/JTCK/SWCLK_37") (pintype "passive"))
    )
    (net (code "33") (name "/SWDIO") (class "Default")
      (node (ref "H1") (pin "2") (pinfunction "2_2") (pintype "passive"))
      (node (ref "U16") (pin "34") (pinfunction "PA13/JTMS/SWDIO_34") (pintype "passive"))
    )
    (net (code "34") (name "/USART1_RX") (class "Default")
      (node (ref "U14") (pin "6") (pinfunction "TXD_6") (pintype "passive"))
      (node (ref "U16") (pin "31") (pinfunction "PA10_31") (pintype "passive"))
    )
    (net (code "35") (name "/USART1_TX") (class "Default")
      (node (ref "U14") (pin "7") (pinfunction "RXD_7") (pintype "passive"))
      (node (ref "U16") (pin "30") (pinfunction "PA9_30") (pintype "passive"))
    )
    (net (code "36") (name "/XI") (class "Default")
      (node (ref "R104") (pin "2") (pinfunction "2_2") (pintype "passive"))
      (node (ref "U16") (pin "12") (pinfunction "PA2_12") (pintype "passive"))
    )
    (net (code "37") (name "3.3V") (class "Default")
      (node (ref "C27") (pin "1") (pinfunction "1_1") (pintype "passive"))
      (node (ref "C36") (pin "2") (pinfunction "2_2") (pintype "passive"))
      (node (ref "C39") (pin "1") (pinfunction "1_1") (pintype "passive"))
      (node (ref "C41") (pin "1") (pinfunction "1_1") (pintype "passive"))
      (node (ref "C46") (pin "1") (pinfunction "1_1") (pintype "passive"))
      (node (ref "C51") (pin "2") (pinfunction "2_2") (pintype "passive"))
      (node (ref "C52") (pin "1") (pinfunction "1_1") (pintype "passive"))
      (node (ref "C59") (pin "2") (pinfunction "2_2") (pintype "passive"))
      (node (ref "H1") (pin "1") (pinfunction "1_1") (pintype "passive"))
      (node (ref "R11") (pin "2") (pinfunction "2_2") (pintype "passive"))
      (node (ref "R12") (pin "2") (pinfunction "2_2") (pintype "passive"))
      (node (ref "R56") (pin "2") (pinfunction "2_2") (pintype "passive"))
      (node (ref "U12") (pin "13") (pinfunction "VDD_13") (pintype "passive"))
      (node (ref "U12") (pin "8") (pinfunction "VLOGIC_8") (pintype "passive"))
      (node (ref "U14") (pin "5") (pinfunction "VCC_5") (pintype "passive"))
      (node (ref "U14") (pin "8") (pinfunction "V3_8") (pintype "passive"))
      (node (ref "U16") (pin "1") (pinfunction "VBAT_1") (pintype "passive"))
      (node (ref "U16") (pin "24") (pinfunction "VDD_1_24") (pintype "passive"))
      (node (ref "U16") (pin "36") (pinfunction "VDD_2_36") (pintype "passive"))
      (node (ref "U16") (pin "48") (pinfunction "VDD_3_48") (pintype "passive"))
      (node (ref "U16") (pin "9") (pinfunction "VDDA_9") (pintype "passive"))
      (node (ref "U18") (pin "2") (pinfunction "2_2") (pintype "passive"))
      (node (ref "U20") (pin "19") (pinfunction "STBY_19") (pintype "passive"))
      (node (ref "U20") (pin "20") (pinfunction "VCC_20") (pintype "passive"))
      (node (ref "U21") (pin "5") (pinfunction "5_5") (pintype "passive"))
      (node (ref "U22") (pin "5") (pinfunction "5_5") (pintype "passive"))
      (node (ref "U24") (pin "2") (pinfunction "VOUT(TAB)_2") (pintype "passive"))
      (node (ref "U24") (pin "4") (pinfunction "TAB_4") (pintype "passive"))
    )
    (net (code "38") (name "<NO NET>") (class "Default")
      (node (ref "C26") (pin "2") (pinfunction "2_2") (pintype "passive"))
      (node (ref "C27") (pin "2") (pinfunction "2_2") (pintype "passive"))
      (node (ref "C35") (pin "1") (pinfunction "1_1") (pintype "passive"))
      (node (ref "C36") (pin "1") (pinfunction "1_1") (pintype "passive"))
      (node (ref "C38") (pin "2") (pinfunction "2_2") (pintype "passive"))
      (node (ref "C39") (pin "2") (pinfunction "2_2") (pintype "passive"))
      (node (ref "C41") (pin "2") (pinfunction "2_2") (pintype "passive"))
      (node (ref "C43") (pin "1") (pinfunction "1_1") (pintype "passive"))
      (node (ref "C46") (pin "2") (pinfunction "2_2") (pintype "passive"))
      (node (ref "C51") (pin "1") (pinfunction "1_1") (pintype "passive"))
      (node (ref "C52") (pin "2") (pinfunction "2_2") (pintype "passive"))
      (node (ref "C53") (pin "2") (pinfunction "2_2") (pintype "passive"))
      (node (ref "C59") (pin "1") (pinfunction "1_1") (pintype "passive"))
      (node (ref "C61") (pin "2") (pinfunction "2_2") (pintype "passive"))
      (node (ref "C62") (pin "2") (pinfunction "2_2") (pintype "passive"))
      (node (ref "C63") (pin "2") (pinfunction "2_2") (pintype "passive"))
      (node (ref "C64") (pin "2") (pinfunction "2_2") (pintype "passive"))
      (node (ref "CN8") (pin "2") (pinfunction "2_2") (pintype "passive"))
      (node (ref "D10") (pin "2") (pinfunction "A_2") (pintype "passive"))
      (node (ref "H1") (pin "4") (pinfunction "4_4") (pintype "passive"))
      (node (ref "Q4") (pin "2") (pinfunction "S_2") (pintype "passive"))
      (node (ref "Q5") (pin "2") (pinfunction "S_2") (pintype "passive"))
      (node (ref "R107") (pin "1") (pinfunction "1_1") (pintype "passive"))
      (node (ref "R111") (pin "1") (pinfunction "1_1") (pintype "passive"))
      (node (ref "R13") (pin "1") (pinfunction "1_1") (pintype "passive"))
      (node (ref "R72") (pin "1") (pinfunction "1_1") (pintype "passive"))
      (node (ref "SW2") (pin "2") (pinfunction "2_2") (pintype "passive"))
      (node (ref "U12") (pin "18") (pinfunction "GND_18") (pintype "passive"))
      (node (ref "U14") (pin "3") (pinfunction "GND_3") (pintype "passive"))
      (node (ref "U16") (pin "20") (pinfunction "PB2/BOOT1_20") (pintype "passive"))
      (node (ref "U16") (pin "23") (pinfunction "VSS_1_23") (pintype "passive"))
      (node (ref "U16") (pin "35") (pinfunction "VSS_2_35") (pintype "passive"))
      (node (ref "U16") (pin "44") (pinfunction "BOOT0_44") (pintype "passive"))
      (node (ref "U16") (pin "47") (pinfunction "VSS_3_47") (pintype "passive"))
      (node (ref "U16") (pin "8") (pinfunction "VSSA_8") (pintype "passive"))
      (node (ref "U18") (pin "1") (pinfunction "1_1") (pintype "passive"))
      (node (ref "U20") (pin "10") (pinfunction "PGND2_10") (pintype "passive"))
      (node (ref "U20") (pin "18") (pinfunction "GND_18") (pintype "passive"))
      (node (ref "U20") (pin "3") (pinfunction "PGND1_3") (pintype "passive"))
      (node (ref "U20") (pin "4") (pinfunction "PGND1_4") (pintype "passive"))
      (node (ref "U20") (pin "9") (pinfunction "PGND2_9") (pintype "passive"))
      (node (ref "U21") (pin "2") (pinfunction "2_2") (pintype "passive"))
      (node (ref "U22") (pin "2") (pinfunction "2_2") (pintype "passive"))
      (node (ref "U24") (pin "1") (pinfunction "ADJ(GND)_1") (pintype "passive"))
      (node (ref "U33") (pin "2") (pinfunction "E_2") (pintype "passive"))
      (node (ref "U35") (pin "2") (pinfunction "E_2") (pintype "passive"))
      (node (ref "U37") (pin "3") (pinfunction "GND_3") (pintype "passive"))
      (node (ref "U37") (pin "5") (pinfunction "ON#/OFF_5") (pintype "passive"))
      (node (ref "U37") (pin "6") (pinfunction "EP_6") (pintype "passive"))
      (node (ref "U38") (pin "1") (pinfunction "C_1") (pintype "passive"))
      (node (ref "USB5") (pin "4") (pinfunction "GND_4") (pintype "passive"))
      (node (ref "USB5") (pin "5") (pinfunction "GND_5") (pintype "passive"))
      (node (ref "USB5") (pin "6") (pinfunction "GND_6") (pintype "passive"))
    )
    (net (code "39") (name "GND") (class "Default")
      (node (ref "C40") (pin "2") (pinfunction "2_2") (pintype "passive"))
      (node (ref "R45") (pin "1") (pinfunction "1_1") (pintype "passive"))
      (node (ref "R61") (pin "1") (pinfunction "1_1") (pintype "passive"))
      (node (ref "R62") (pin "2") (pinfunction "2_2") (pintype "passive"))
      (node (ref "USB3") (pin "A1") (pinfunction "GND_A1") (pintype "passive"))
      (node (ref "USB3") (pin "A12") (pinfunction "GND_A12") (pintype "passive"))
      (node (ref "USB3") (pin "B1") (pinfunction "GND_B1") (pintype "passive"))
      (node (ref "USB3") (pin "B12") (pinfunction "GND_B12") (pintype "passive"))
    )
    (net (code "40") (name "Net-(C40-Pad1)") (class "Default")
      (node (ref "C40") (pin "1") (pinfunction "1_1") (pintype "passive"))
      (node (ref "R45") (pin "2") (pinfunction "2_2") (pintype "passive"))
      (node (ref "USB3") (pin "1") (pinfunction "EP_1") (pintype "passive"))
      (node (ref "USB3") (pin "2") (pinfunction "EP_2") (pintype "passive"))
      (node (ref "USB3") (pin "3") (pinfunction "EP_3") (pintype "passive"))
      (node (ref "USB3") (pin "4") (pinfunction "EP_4") (pintype "passive"))
    )
    (net (code "41") (name "Net-(D10-K)") (class "Default")
      (node (ref "D10") (pin "1") (pinfunction "K_1") (pintype "passive"))
      (node (ref "L2") (pin "2") (pinfunction "2_2") (pintype "passive"))
      (node (ref "U37") (pin "2") (pinfunction "OUT_2") (pintype "passive"))
    )
    (net (code "42") (name "Net-(D11-A)") (class "Default")
      (node (ref "CN5") (pin "2") (pinfunction "2_2") (pintype "passive"))
      (node (ref "D11") (pin "2") (pinfunction "A_2") (pintype "passive"))
      (node (ref "Q4") (pin "3") (pinfunction "D_3") (pintype "passive"))
    )
    (net (code "43") (name "Net-(D12-A)") (class "Default")
      (node (ref "CN6") (pin "2") (pinfunction "2_2") (pintype "passive"))
      (node (ref "CN7") (pin "1") (pinfunction "1_1") (pintype "passive"))
      (node (ref "D12") (pin "2") (pinfunction "A_2") (pintype "passive"))
      (node (ref "Q5") (pin "3") (pinfunction "D_3") (pintype "passive"))
    )
    (net (code "44") (name "Net-(Q4-G)") (class "Default")
      (node (ref "Q4") (pin "1") (pinfunction "G_1") (pintype "passive"))
      (node (ref "R106") (pin "1") (pinfunction "1_1") (pintype "passive"))
      (node (ref "R107") (pin "2") (pinfunction "2_2") (pintype "passive"))
    )
    (net (code "45") (name "Net-(Q5-G)") (class "Default")
      (node (ref "Q5") (pin "1") (pinfunction "G_1") (pintype "passive"))
      (node (ref "R110") (pin "1") (pinfunction "1_1") (pintype "passive"))
      (node (ref "R111") (pin "2") (pinfunction "2_2") (pintype "passive"))
    )
    (net (code "46") (name "Net-(U12-AD0)") (class "Default")
      (node (ref "R13") (pin "2") (pinfunction "2_2") (pintype "passive"))
      (node (ref "U12") (pin "9") (pinfunction "AD0_9") (pintype "passive"))
    )
    (net (code "47") (name "Net-(U12-CPOUT)") (class "Default")
      (node (ref "C53") (pin "1") (pinfunction "1_1") (pintype "passive"))
      (node (ref "U12") (pin "20") (pinfunction "CPOUT_20") (pintype "passive"))
    )
    (net (code "48") (name "Net-(U12-REGOUT)") (class "Default")
      (node (ref "C35") (pin "2") (pinfunction "2_2") (pintype "passive"))
      (node (ref "U12") (pin "10") (pinfunction "REGOUT_10") (pintype "passive"))
    )
    (net (code "49") (name "Net-(U33-B)") (class "Default")
      (node (ref "R104") (pin "1") (pinfunction "1_1") (pintype "passive"))
      (node (ref "U33") (pin "1") (pinfunction "B_1") (pintype "passive"))
    )
    (net (code "50") (name "Net-(U33-C)") (class "Default")
      (node (ref "R105") (pin "1") (pinfunction "1_1") (pintype "passive"))
      (node (ref "U33") (pin "3") (pinfunction "C_3") (pintype "passive"))
    )
    (net (code "51") (name "Net-(U34-B)") (class "Default")
      (node (ref "R105") (pin "2") (pinfunction "2_2") (pintype "passive"))
      (node (ref "U34") (pin "1") (pinfunction "B_1") (pintype "passive"))
    )
    (net (code "52") (name "Net-(U34-C)") (class "Default")
      (node (ref "R106") (pin "2") (pinfunction "2_2") (pintype "passive"))
      (node (ref "U34") (pin "3") (pinfunction "C_3") (pintype "passive"))
    )
    (net (code "53") (name "Net-(U35-B)") (class "Default")
      (node (ref "R108") (pin "1") (pinfunction "1_1") (pintype "passive"))
      (node (ref "U35") (pin "1") (pinfunction "B_1") (pintype "passive"))
    )
    (net (code "54") (name "Net-(U35-C)") (class "Default")
      (node (ref "R109") (pin "1") (pinfunction "1_1") (pintype "passive"))
      (node (ref "U35") (pin "3") (pinfunction "C_3") (pintype "passive"))
    )
    (net (code "55") (name "Net-(U36-B)") (class "Default")
      (node (ref "R109") (pin "2") (pinfunction "2_2") (pintype "passive"))
      (node (ref "U36") (pin "1") (pinfunction "B_1") (pintype "passive"))
    )
    (net (code "56") (name "Net-(U36-C)") (class "Default")
      (node (ref "R110") (pin "2") (pinfunction "2_2") (pintype "passive"))
      (node (ref "U36") (pin "3") (pinfunction "C_3") (pintype "passive"))
    )
    (net (code "57") (name "Net-(U38-A)") (class "Default")
      (node (ref "R112") (pin "1") (pinfunction "1_1") (pintype "passive"))
      (node (ref "U38") (pin "2") (pinfunction "A_2") (pintype "passive"))
    )
    (net (code "58") (name "Net-(USB3-CC1)") (class "Default")
      (node (ref "R61") (pin "2") (pinfunction "2_2") (pintype "passive"))
      (node (ref "USB3") (pin "A5") (pinfunction "CC1_A5") (pintype "passive"))
    )
    (net (code "59") (name "Net-(USB3-CC2)") (class "Default")
      (node (ref "R62") (pin "1") (pinfunction "1_1") (pintype "passive"))
      (node (ref "USB3") (pin "B5") (pinfunction "CC2_B5") (pintype "passive"))
    )
    (net (code "60") (name "SW") (class "Default")
      (node (ref "C61") (pin "1") (pinfunction "1_1") (pintype "passive"))
      (node (ref "C63") (pin "1") (pinfunction "1_1") (pintype "passive"))
      (node (ref "CN5") (pin "1") (pinfunction "1_1") (pintype "passive"))
      (node (ref "CN6") (pin "1") (pinfunction "1_1") (pintype "passive"))
      (node (ref "CN7") (pin "2") (pinfunction "2_2") (pintype "passive"))
      (node (ref "D11") (pin "1") (pinfunction "K_1") (pintype "passive"))
      (node (ref "D12") (pin "1") (pinfunction "K_1") (pintype "passive"))
      (node (ref "R71") (pin "2") (pinfunction "2_2") (pintype "passive"))
      (node (ref "U20") (pin "13") (pinfunction "VM2_13") (pintype "passive"))
      (node (ref "U20") (pin "14") (pinfunction "VM3_14") (pintype "passive"))
      (node (ref "U20") (pin "24") (pinfunction "VM1_24") (pintype "passive"))
      (node (ref "U34") (pin "2") (pinfunction "E_2") (pintype "passive"))
      (node (ref "U36") (pin "2") (pinfunction "E_2") (pintype "passive"))
      (node (ref "U37") (pin "1") (pinfunction "VIN_1") (pintype "passive"))
    )
    (net (code "61") (name "VBAT") (class "Default")
      (node (ref "CN8") (pin "1") (pinfunction "1_1") (pintype "passive"))
      (node (ref "R112") (pin "2") (pinfunction "2_2") (pintype "passive"))
    )
    (net (code "62") (name "unconnected-(U12-AUX_CL-Pad7)") (class "Default")
      (node (ref "U12") (pin "7") (pinfunction "AUX_CL_7") (pintype "passive+no_connect"))
    )
    (net (code "63") (name "unconnected-(U12-AUX_DA-Pad6)") (class "Default")
      (node (ref "U12") (pin "6") (pinfunction "AUX_DA_6") (pintype "passive+no_connect"))
    )
    (net (code "64") (name "unconnected-(U12-CLKIN-Pad1)") (class "Default")
      (node (ref "U12") (pin "1") (pinfunction "CLKIN_1") (pintype "passive+no_connect"))
    )
    (net (code "65") (name "unconnected-(U12-EP-Pad25)") (class "Default")
      (node (ref "U12") (pin "25") (pinfunction "EP_25") (pintype "passive+no_connect"))
    )
    (net (code "66") (name "unconnected-(U12-FSYNC-Pad11)") (class "Default")
      (node (ref "U12") (pin "11") (pinfunction "FSYNC_11") (pintype "passive+no_connect"))
    )
    (net (code "67") (name "unconnected-(U12-INT-Pad12)") (class "Default")
      (node (ref "U12") (pin "12") (pinfunction "INT_12") (pintype "passive+no_connect"))
    )
    (net (code "68") (name "unconnected-(U12-NC-Pad2)") (class "Default")
      (node (ref "U12") (pin "2") (pinfunction "NC_2") (pintype "passive+no_connect"))
    )
    (net (code "69") (name "unconnected-(U12-NC-Pad3)") (class "Default")
      (node (ref "U12") (pin "3") (pinfunction "NC_3") (pintype "passive+no_connect"))
    )
    (net (code "70") (name "unconnected-(U12-NC-Pad4)") (class "Default")
      (node (ref "U12") (pin "4") (pinfunction "NC_4") (pintype "passive+no_connect"))
    )
    (net (code "71") (name "unconnected-(U12-NC-Pad5)") (class "Default")
      (node (ref "U12") (pin "5") (pinfunction "NC_5") (pintype "passive+no_connect"))
    )
    (net (code "72") (name "unconnected-(U12-NC-Pad14)") (class "Default")
      (node (ref "U12") (pin "14") (pinfunction "NC_14") (pintype "passive+no_connect"))
    )
    (net (code "73") (name "unconnected-(U12-NC-Pad15)") (class "Default")
      (node (ref "U12") (pin "15") (pinfunction "NC_15") (pintype "passive+no_connect"))
    )
    (net (code "74") (name "unconnected-(U12-NC-Pad16)") (class "Default")
      (node (ref "U12") (pin "16") (pinfunction "NC_16") (pintype "passive+no_connect"))
    )
    (net (code "75") (name "unconnected-(U12-NC-Pad17)") (class "Default")
      (node (ref "U12") (pin "17") (pinfunction "NC_17") (pintype "passive+no_connect"))
    )
    (net (code "76") (name "unconnected-(U12-RESV-Pad19)") (class "Default")
      (node (ref "U12") (pin "19") (pinfunction "RESV_19") (pintype "passive+no_connect"))
    )
    (net (code "77") (name "unconnected-(U12-RESV-Pad21)") (class "Default")
      (node (ref "U12") (pin "21") (pinfunction "RESV_21") (pintype "passive+no_connect"))
    )
    (net (code "78") (name "unconnected-(U12-RESV-Pad22)") (class "Default")
      (node (ref "U12") (pin "22") (pinfunction "RESV_22") (pintype "passive+no_connect"))
    )
    (net (code "79") (name "unconnected-(U14-RTS#-Pad4)") (class "Default")
      (node (ref "U14") (pin "4") (pinfunction "RTS#_4") (pintype "passive+no_connect"))
    )
    (net (code "80") (name "unconnected-(U16-PA1-Pad11)") (class "Default")
      (node (ref "U16") (pin "11") (pinfunction "PA1_11") (pintype "passive+no_connect"))
    )
    (net (code "81") (name "unconnected-(U16-PA6-Pad16)") (class "Default")
      (node (ref "U16") (pin "16") (pinfunction "PA6_16") (pintype "passive+no_connect"))
    )
    (net (code "82") (name "unconnected-(U16-PA8-Pad29)") (class "Default")
      (node (ref "U16") (pin "29") (pinfunction "PA8_29") (pintype "passive+no_connect"))
    )
    (net (code "83") (name "unconnected-(U16-PA12-Pad33)") (class "Default")
      (node (ref "U16") (pin "33") (pinfunction "PA12_33") (pintype "passive+no_connect"))
    )
    (net (code "84") (name "unconnected-(U16-PB11-Pad22)") (class "Default")
      (node (ref "U16") (pin "22") (pinfunction "PB11_22") (pintype "passive+no_connect"))
    )
    (net (code "85") (name "unconnected-(U16-PC13-TAMPER-RTC-Pad2)") (class "Default")
      (node (ref "U16") (pin "2") (pinfunction "PC13-TAMPER-RTC_2") (pintype "passive+no_connect"))
    )
    (net (code "86") (name "unconnected-(U16-PC14-OSC32_IN-Pad3)") (class "Default")
      (node (ref "U16") (pin "3") (pinfunction "PC14-OSC32_IN_3") (pintype "passive+no_connect"))
    )
    (net (code "87") (name "unconnected-(U16-PC15-OSC32_OUT-Pad4)") (class "Default")
      (node (ref "U16") (pin "4") (pinfunction "PC15-OSC32_OUT_4") (pintype "passive+no_connect"))
    )
    (net (code "88") (name "unconnected-(USB3-SUB1-PadA8)") (class "Default")
      (node (ref "USB3") (pin "A8") (pinfunction "SUB1_A8") (pintype "passive+no_connect"))
    )
    (net (code "89") (name "unconnected-(USB3-SUB2-PadB8)") (class "Default")
      (node (ref "USB3") (pin "B8") (pinfunction "SUB2_B8") (pintype "passive+no_connect"))
    )
    (net (code "90") (name "unconnected-(USB3-VBUS-PadA4)") (class "Default")
      (node (ref "USB3") (pin "A4") (pinfunction "VBUS_A4") (pintype "passive+no_connect"))
    )
    (net (code "91") (name "unconnected-(USB3-VBUS-PadA9)") (class "Default")
      (node (ref "USB3") (pin "A9") (pinfunction "VBUS_A9") (pintype "passive+no_connect"))
    )
    (net (code "92") (name "unconnected-(USB3-VBUS-PadB4)") (class "Default")
      (node (ref "USB3") (pin "B4") (pinfunction "VBUS_B4") (pintype "passive+no_connect"))
    )
    (net (code "93") (name "unconnected-(USB3-VBUS-PadB9)") (class "Default")
      (node (ref "USB3") (pin "B9") (pinfunction "VBUS_B9") (pintype "passive+no_connect"))
    )
    (net (code "94") (name "unconnected-(USB5-D+-Pad3)") (class "Default")
      (node (ref "USB5") (pin "3") (pinfunction "D+_3") (pintype "passive+no_connect"))
    )
    (net (code "95") (name "unconnected-(USB5-D--Pad2)") (class "Default")
      (node (ref "USB5") (pin "2") (pinfunction "D-_2") (pintype "passive+no_connect"))
    )
  )
)
